# LM317-Adjustable-Power-Supply-EasyEDA.net
KiCad netlist of a schematic drawn in EasyEDA
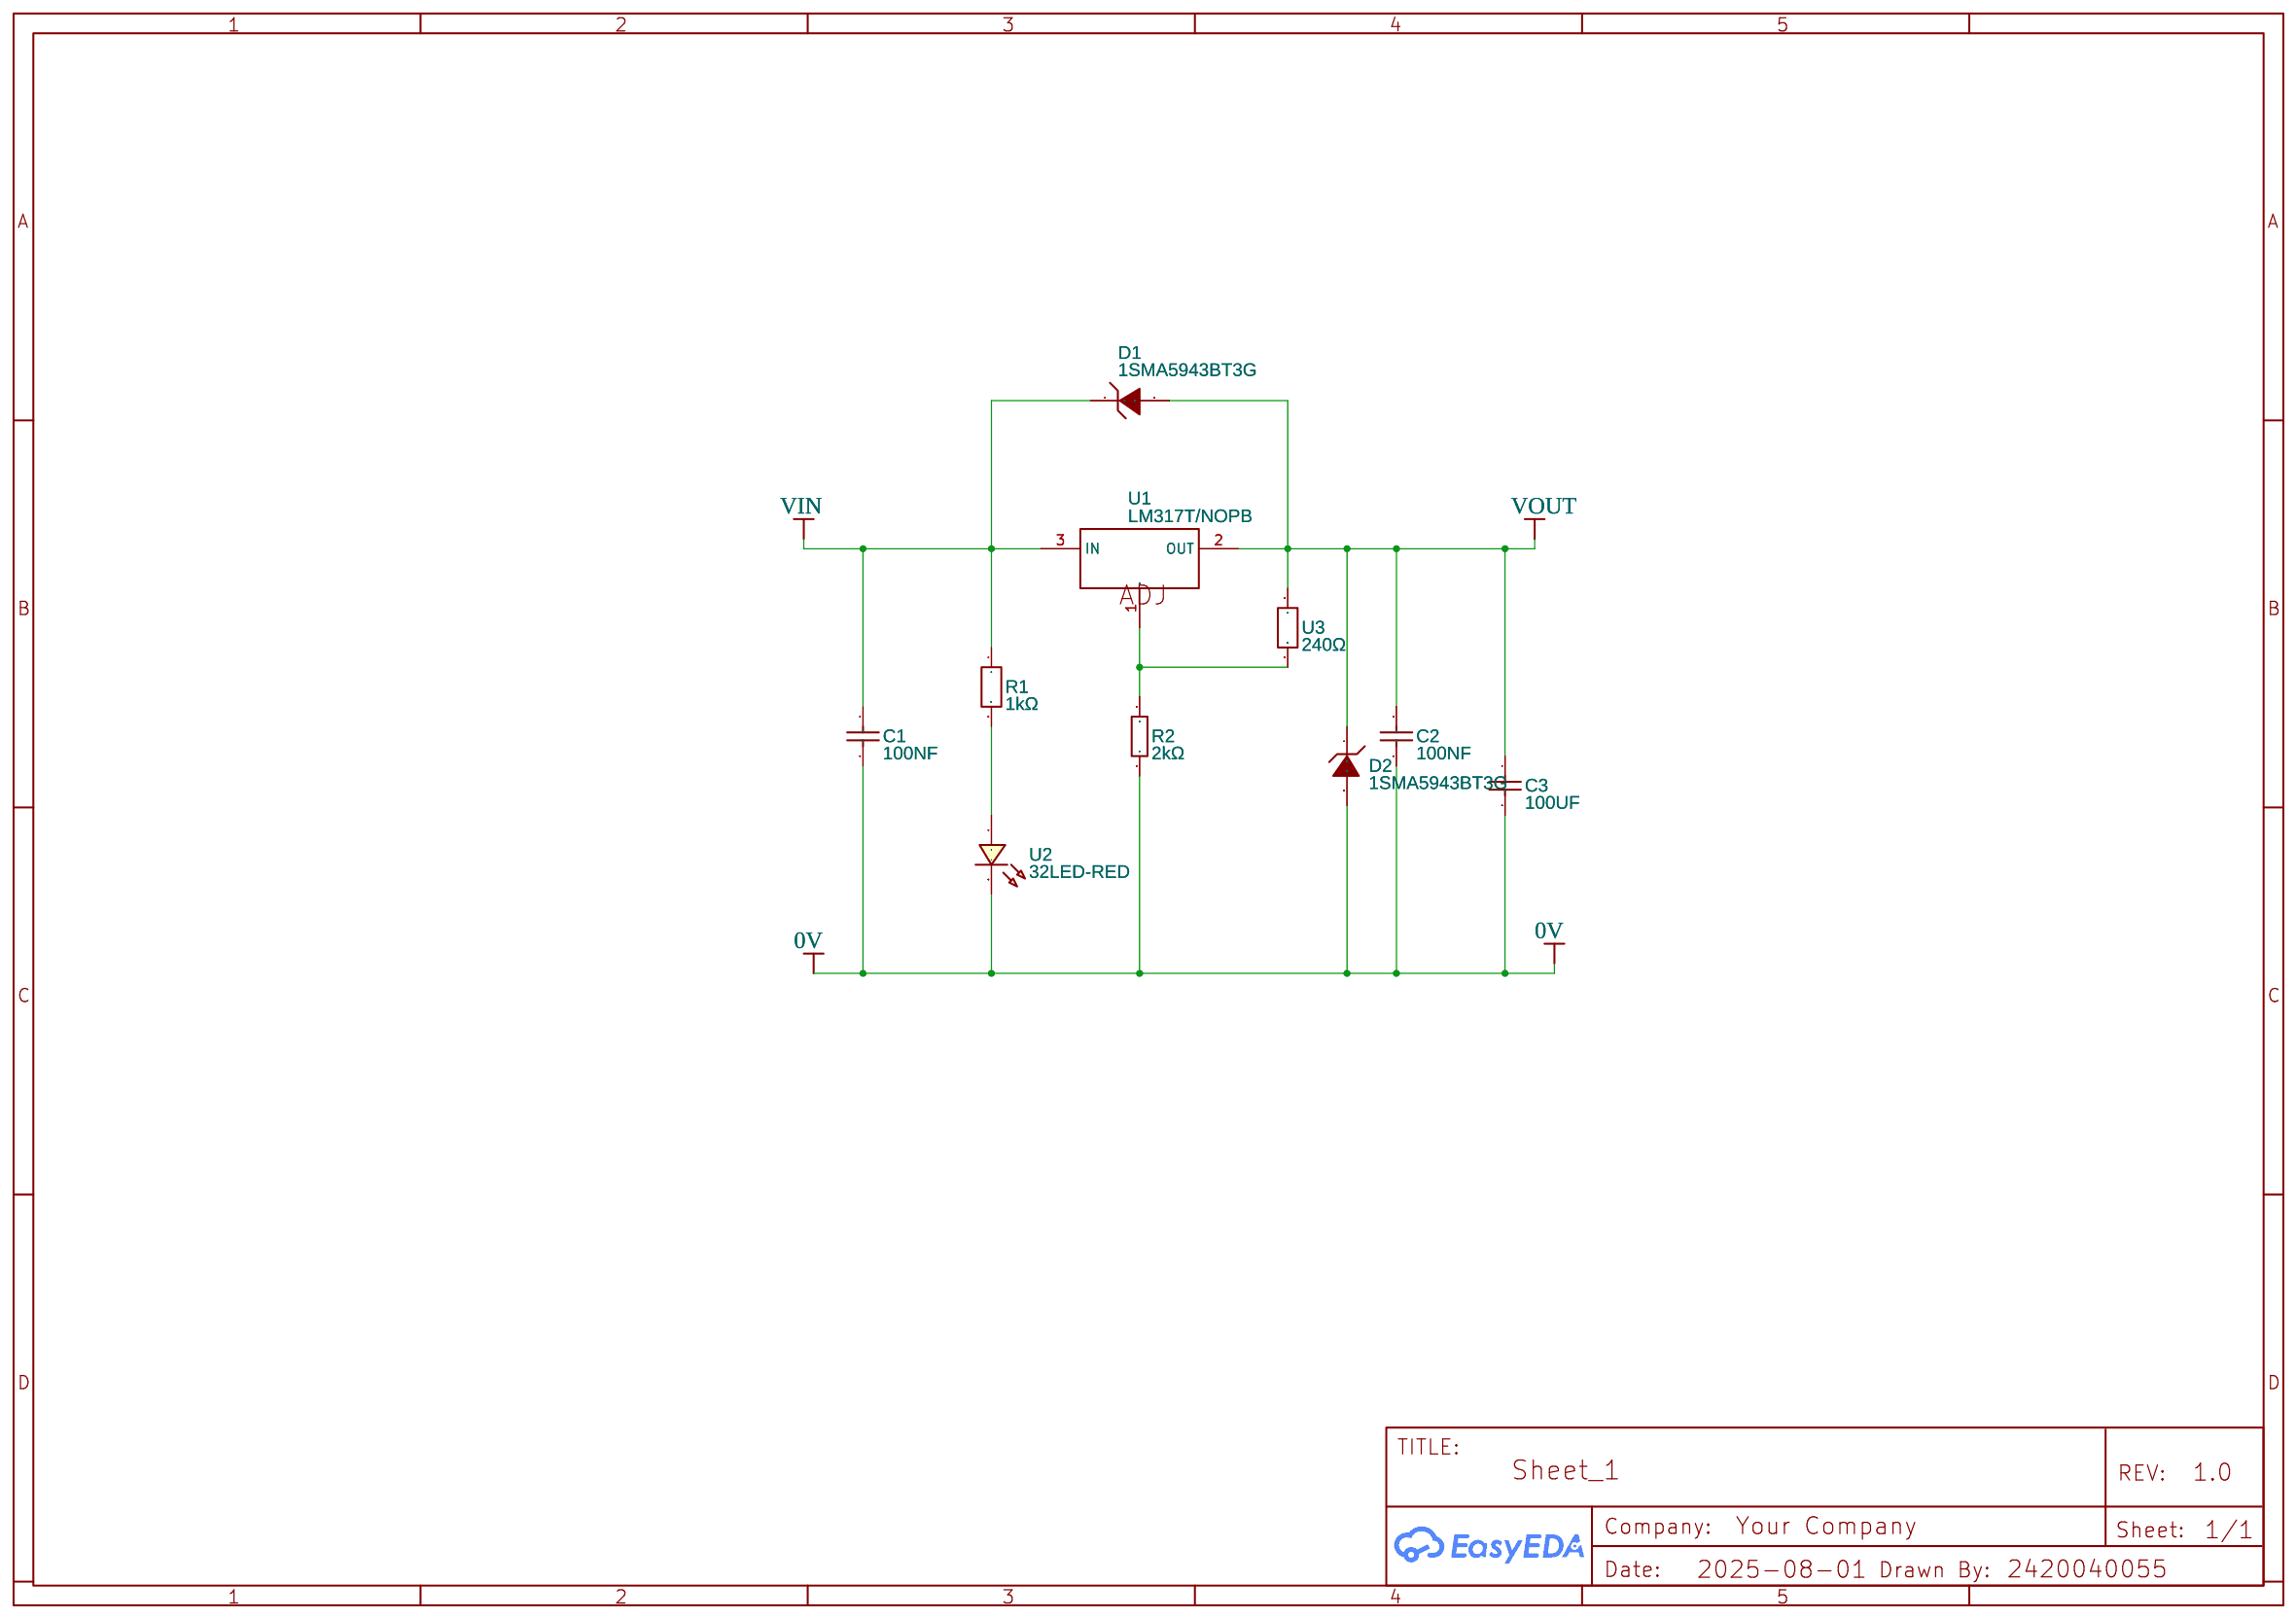
[diagram p0: schematic sheet]

(export (version "E")
  (design (tool "Eeschema 10.0.6"))
  (components
    (comp (ref "C1")
      (value "100NF")
      (fields (field (name "Manufacturer Part") "电容15nf100v"))
      (libsource (lib "") (part "CAPACITOR15NF100V"))
    )
    (comp (ref "C2")
      (value "100NF")
      (fields (field (name "Manufacturer Part") "电容15nf100v"))
      (libsource (lib "") (part "CAPACITOR15NF100V"))
    )
    (comp (ref "C3")
      (value "100UF")
      (fields (field (name "Manufacturer Part") "电容15nf100v"))
      (libsource (lib "") (part "CAPACITOR15NF100V"))
    )
    (comp (ref "D1")
      (value "1SMA5943BT3G")
      (fields (field (name "Manufacturer") "onsemi(安森美)"))
      (libsource (lib "") (part "1SMA5943BT3G_1"))
    )
    (comp (ref "D2")
      (value "1SMA5943BT3G")
      (fields (field (name "Manufacturer") "onsemi(安森美)"))
      (libsource (lib "") (part "1SMA5943BT3G"))
    )
    (comp (ref "R1")
      (value "1kΩ")
      (fields (field (name "Manufacturer Part") "RWS10 1K J TR") (field (name "Manufacturer") "Ohmite"))
      (libsource (lib "") (part "RWS10 1K J TR"))
    )
    (comp (ref "R2")
      (value "2kΩ")
      (fields (field (name "Manufacturer Part") "MFR200FRF52-2K") (field (name "Manufacturer") "YAGEO(国巨)"))
      (libsource (lib "") (part "MFR200FRF52-2K"))
    )
    (comp (ref "U1")
      (value "LM317T/NOPB")
      (fields (field (name "Manufacturer") "TI(德州仪器)"))
      (libsource (lib "") (part "LM317T/NOPB"))
    )
    (comp (ref "U2")
      (value "32LED-RED")
      (fields (field (name "Manufacturer") "Grayhill"))
      (libsource (lib "") (part "32LED-RED"))
    )
    (comp (ref "U3")
      (value "240Ω")
      (fields (field (name "Manufacturer Part") "90J240E") (field (name "Manufacturer") "Ohmite"))
      (libsource (lib "") (part "90J240E"))
    )
  )
  (nets
    (net (code "1") (name "0V") (class "Default")
      (node (ref "C1") (pin "2") (pinfunction "2_2") (pintype "input"))
      (node (ref "C2") (pin "2") (pinfunction "2_2") (pintype "input"))
      (node (ref "C3") (pin "2") (pinfunction "2_2") (pintype "input"))
      (node (ref "D2") (pin "2") (pinfunction "A_2") (pintype "unspecified"))
      (node (ref "R2") (pin "2") (pinfunction "2_2") (pintype "unspecified"))
      (node (ref "U2") (pin "2") (pinfunction "-_2") (pintype "unspecified"))
    )
    (net (code "2") (name "Net-(U1-ADJ)") (class "Default")
      (node (ref "R2") (pin "1") (pinfunction "1_1") (pintype "unspecified"))
      (node (ref "U1") (pin "1") (pinfunction "ADJ_1") (pintype "passive"))
      (node (ref "U3") (pin "2") (pinfunction "2_2") (pintype "unspecified"))
    )
    (net (code "3") (name "Net-(U2-+)") (class "Default")
      (node (ref "R1") (pin "2") (pinfunction "2_2") (pintype "unspecified"))
      (node (ref "U2") (pin "1") (pinfunction "+_1") (pintype "unspecified"))
    )
    (net (code "4") (name "VIN") (class "Default")
      (node (ref "C1") (pin "1") (pinfunction "1_1") (pintype "input"))
      (node (ref "D1") (pin "1") (pinfunction "C_1") (pintype "unspecified"))
      (node (ref "R1") (pin "1") (pinfunction "1_1") (pintype "unspecified"))
      (node (ref "U1") (pin "3") (pinfunction "IN_3") (pintype "passive"))
    )
    (net (code "5") (name "VOUT") (class "Default")
      (node (ref "C2") (pin "1") (pinfunction "1_1") (pintype "input"))
      (node (ref "C3") (pin "1") (pinfunction "1_1") (pintype "input"))
      (node (ref "D1") (pin "2") (pinfunction "A_2") (pintype "unspecified"))
      (node (ref "D2") (pin "1") (pinfunction "C_1") (pintype "unspecified"))
      (node (ref "U1") (pin "2") (pinfunction "OUT_2") (pintype "passive"))
      (node (ref "U3") (pin "1") (pinfunction "1_1") (pintype "unspecified"))
    )
  )
)
